# ignatova_telemetry_board.net
KiCad netlist of a schematic drawn in Altium Designer
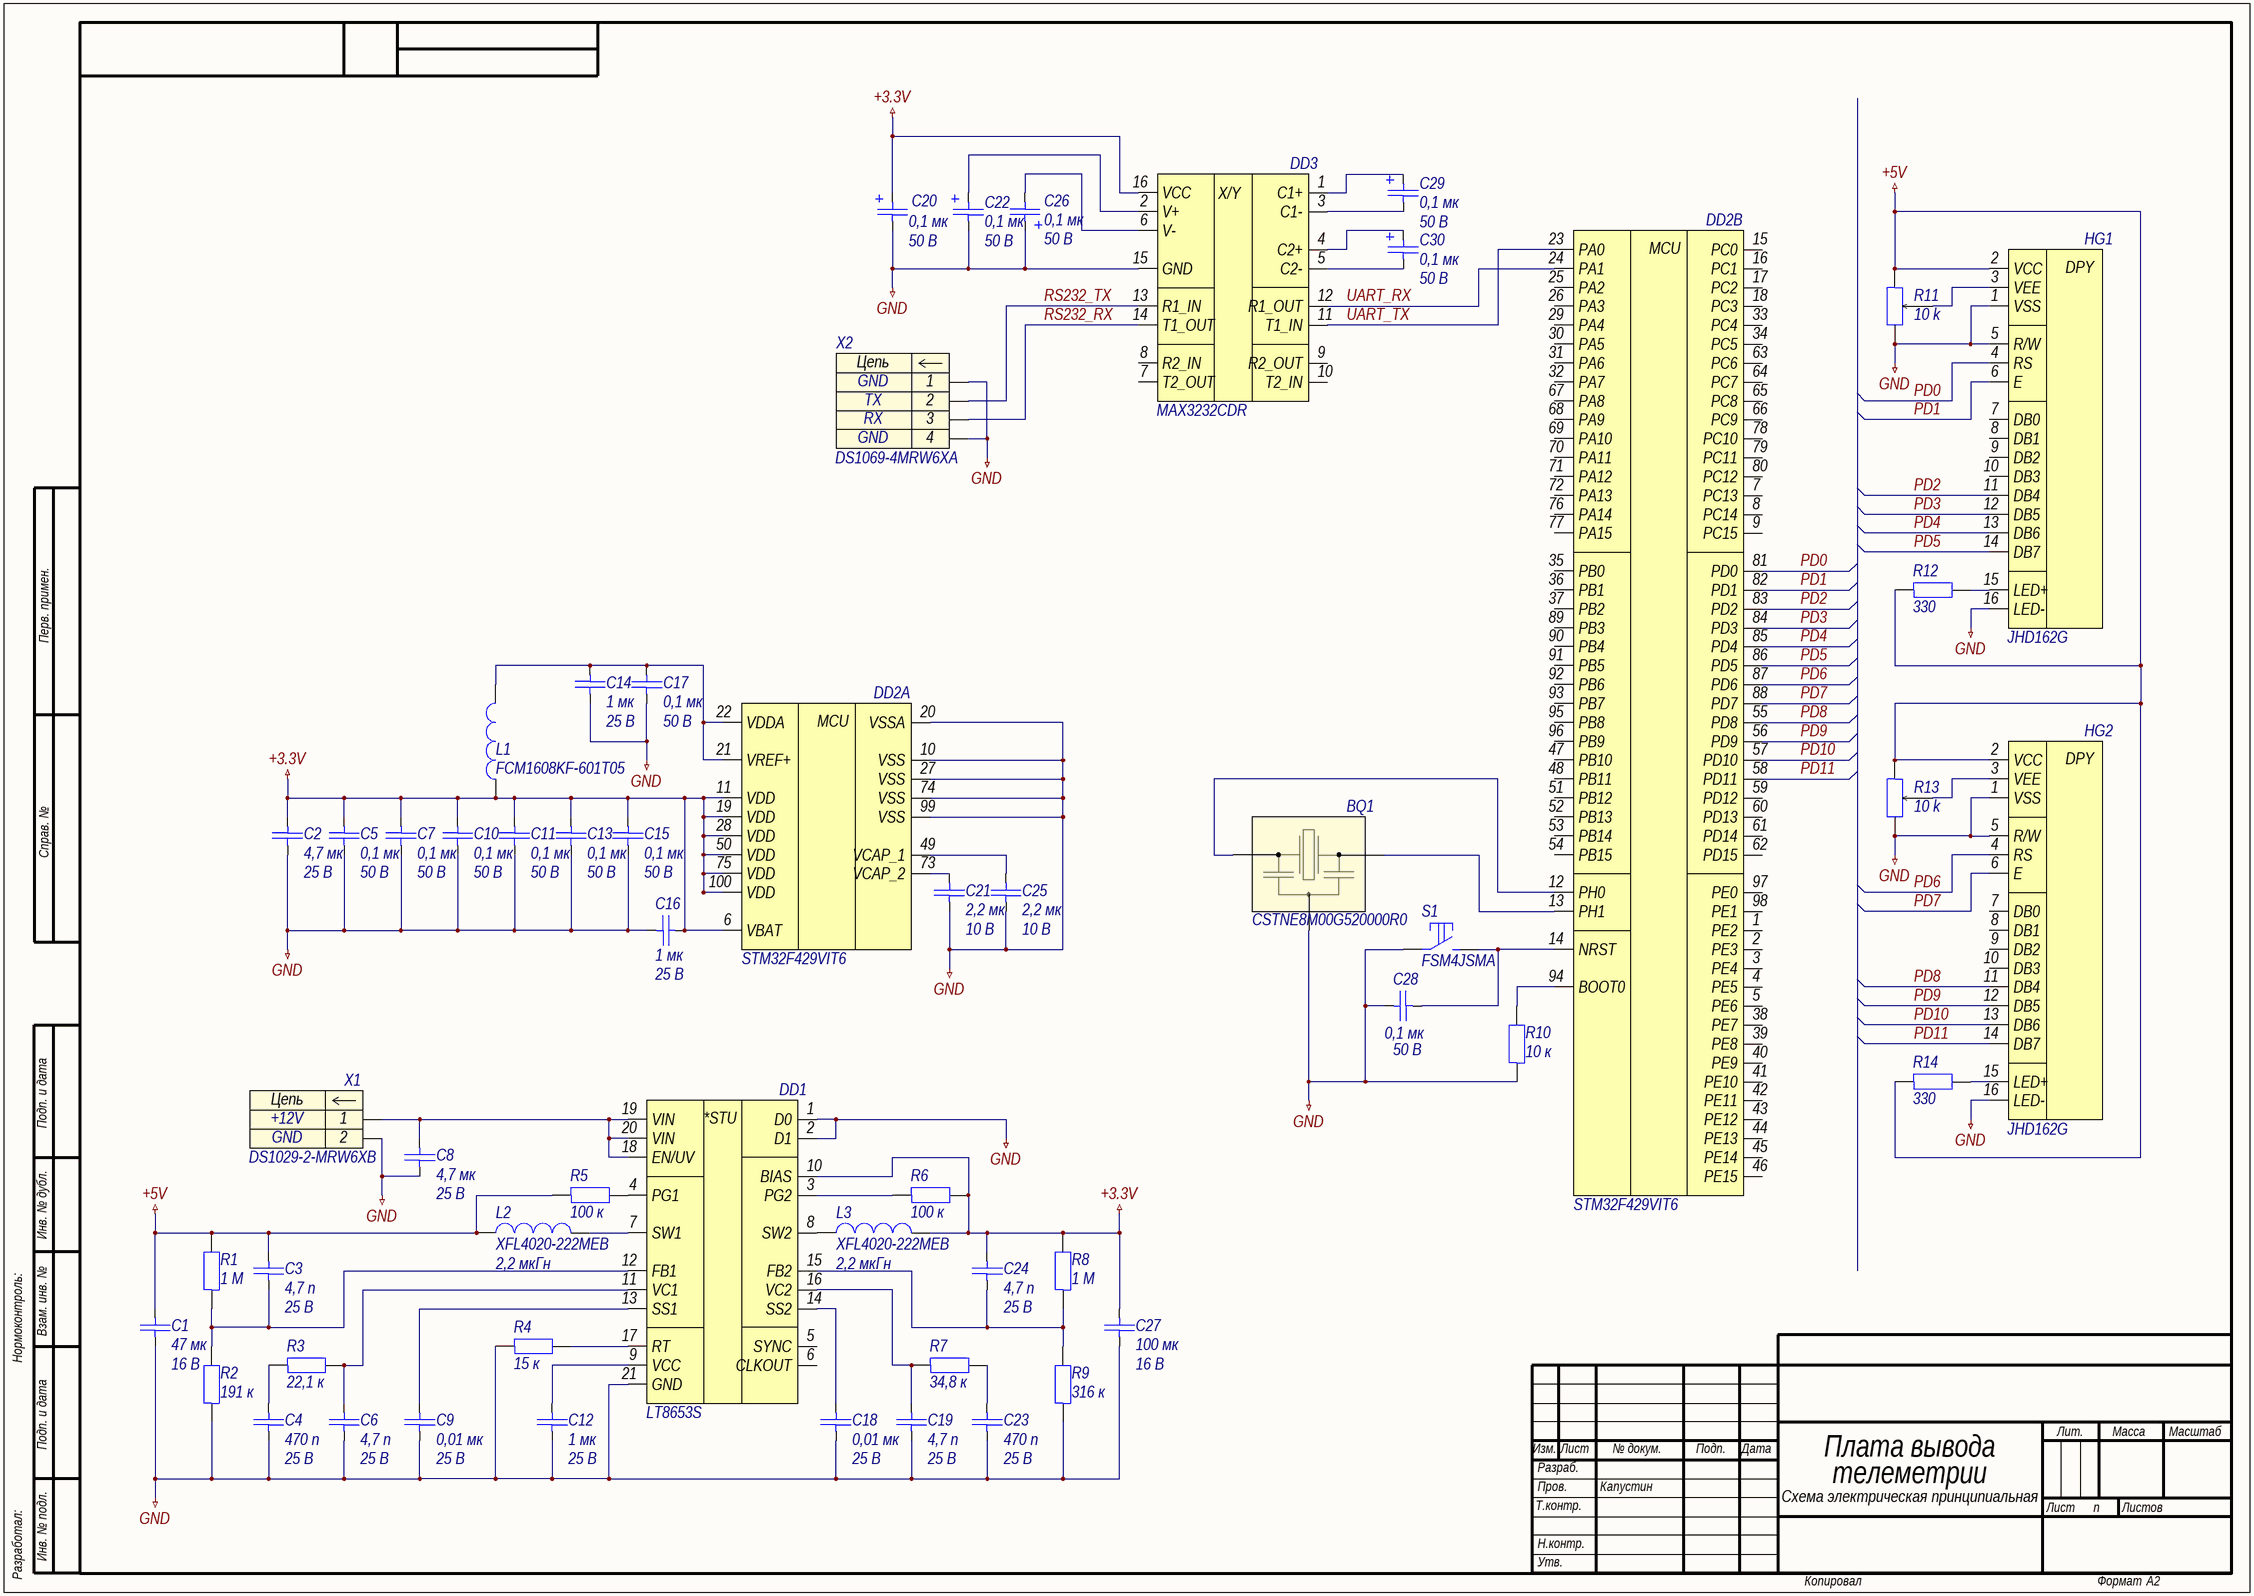
[diagram p0: ignatova_telemetry_board.SchDoc]

(export (version "E")
  (design (tool "Eeschema 10.0.6"))
  (components
    (comp (ref "BQ1")
      (value "CSTNE8M00G520000R0")
      (footprint "CSTNE-3-320X130X70")
      (description "=Описание")
      (libsource (lib "Database_Students") (part "CSTNE8M00G520000R0"))
    )
    (comp (ref "C1")
      (value "47 мк")
      (footprint "C1210")
      (description "=Описание")
      (fields (field (name "НАПРЯЖЕНИЕ") "16 В"))
      (libsource (lib "Database_Students") (part "C-NONPOLAR"))
    )
    (comp (ref "C2")
      (value "4,7 мк")
      (footprint "C0603")
      (description "=Описание")
      (fields (field (name "НАПРЯЖЕНИЕ") "25 В"))
      (libsource (lib "Database_Students") (part "C-NONPOLAR"))
    )
    (comp (ref "C3")
      (value "4,7 п")
      (footprint "C0201")
      (description "=Описание")
      (fields (field (name "НАПРЯЖЕНИЕ") "25 В"))
      (libsource (lib "Database_Students") (part "C-NONPOLAR"))
    )
    (comp (ref "C4")
      (value "470 п")
      (footprint "C0201")
      (description "=Описание")
      (fields (field (name "НАПРЯЖЕНИЕ") "25 В"))
      (libsource (lib "Database_Students") (part "C-NONPOLAR"))
    )
    (comp (ref "C5")
      (value "0,1 мк")
      (footprint "C0603")
      (description "=Описание")
      (fields (field (name "НАПРЯЖЕНИЕ") "50 В"))
      (libsource (lib "Database_Students") (part "C-NONPOLAR"))
    )
    (comp (ref "C6")
      (value "4,7 п")
      (footprint "C0201")
      (description "=Описание")
      (fields (field (name "НАПРЯЖЕНИЕ") "25 В"))
      (libsource (lib "Database_Students") (part "C-NONPOLAR"))
    )
    (comp (ref "C7")
      (value "0,1 мк")
      (footprint "C0603")
      (description "=Описание")
      (fields (field (name "НАПРЯЖЕНИЕ") "50 В"))
      (libsource (lib "Database_Students") (part "C-NONPOLAR"))
    )
    (comp (ref "C8")
      (value "4,7 мк")
      (footprint "C0603")
      (description "=Описание")
      (fields (field (name "НАПРЯЖЕНИЕ") "25 В"))
      (libsource (lib "Database_Students") (part "C-NONPOLAR"))
    )
    (comp (ref "C9")
      (value "0,01 мк")
      (footprint "C0201")
      (description "=Описание")
      (fields (field (name "НАПРЯЖЕНИЕ") "25 В"))
      (libsource (lib "Database_Students") (part "C-NONPOLAR"))
    )
    (comp (ref "C10")
      (value "0,1 мк")
      (footprint "C0603")
      (description "=Описание")
      (fields (field (name "НАПРЯЖЕНИЕ") "50 В"))
      (libsource (lib "Database_Students") (part "C-NONPOLAR"))
    )
    (comp (ref "C11")
      (value "0,1 мк")
      (footprint "C0603")
      (description "=Описание")
      (fields (field (name "НАПРЯЖЕНИЕ") "50 В"))
      (libsource (lib "Database_Students") (part "C-NONPOLAR"))
    )
    (comp (ref "C12")
      (value "1 мк")
      (footprint "C0603")
      (description "=Описание")
      (fields (field (name "НАПРЯЖЕНИЕ") "25 В"))
      (libsource (lib "Database_Students") (part "C-NONPOLAR"))
    )
    (comp (ref "C13")
      (value "0,1 мк")
      (footprint "C0603")
      (description "=Описание")
      (fields (field (name "НАПРЯЖЕНИЕ") "50 В"))
      (libsource (lib "Database_Students") (part "C-NONPOLAR"))
    )
    (comp (ref "C14")
      (value "1 мк")
      (footprint "C0603")
      (description "=Описание")
      (fields (field (name "НАПРЯЖЕНИЕ") "25 В"))
      (libsource (lib "Database_Students") (part "C-NONPOLAR"))
    )
    (comp (ref "C15")
      (value "0,1 мк")
      (footprint "C0603")
      (description "=Описание")
      (fields (field (name "НАПРЯЖЕНИЕ") "50 В"))
      (libsource (lib "Database_Students") (part "C-NONPOLAR"))
    )
    (comp (ref "C16")
      (value "1 мк")
      (footprint "C0603")
      (description "=Описание")
      (fields (field (name "НАПРЯЖЕНИЕ") "25 В"))
      (libsource (lib "Database_Students") (part "C-NONPOLAR"))
    )
    (comp (ref "C17")
      (value "0,1 мк")
      (footprint "C0603")
      (description "=Описание")
      (fields (field (name "НАПРЯЖЕНИЕ") "50 В"))
      (libsource (lib "Database_Students") (part "C-NONPOLAR"))
    )
    (comp (ref "C18")
      (value "0,01 мк")
      (footprint "C0201")
      (description "=Описание")
      (fields (field (name "НАПРЯЖЕНИЕ") "25 В"))
      (libsource (lib "Database_Students") (part "C-NONPOLAR"))
    )
    (comp (ref "C19")
      (value "4,7 п")
      (footprint "C0201")
      (description "=Описание")
      (fields (field (name "НАПРЯЖЕНИЕ") "25 В"))
      (libsource (lib "Database_Students") (part "C-NONPOLAR"))
    )
    (comp (ref "C20")
      (value "0,1 мк")
      (footprint "C1206POLAR")
      (description "=Описание")
      (fields (field (name "НАПРЯЖЕНИЕ") "50 В"))
      (libsource (lib "Database_Students") (part "C-POLAR"))
    )
    (comp (ref "C21")
      (value "2,2 мк")
      (footprint "C0603")
      (description "=Описание")
      (fields (field (name "НАПРЯЖЕНИЕ") "10 В"))
      (libsource (lib "Database_Students") (part "C-NONPOLAR"))
    )
    (comp (ref "C22")
      (value "0,1 мк")
      (footprint "C1206POLAR")
      (description "=Описание")
      (fields (field (name "НАПРЯЖЕНИЕ") "50 В"))
      (libsource (lib "Database_Students") (part "C-POLAR"))
    )
    (comp (ref "C23")
      (value "470 п")
      (footprint "C0201")
      (description "=Описание")
      (fields (field (name "НАПРЯЖЕНИЕ") "25 В"))
      (libsource (lib "Database_Students") (part "C-NONPOLAR"))
    )
    (comp (ref "C24")
      (value "4,7 п")
      (footprint "C0201")
      (description "=Описание")
      (fields (field (name "НАПРЯЖЕНИЕ") "25 В"))
      (libsource (lib "Database_Students") (part "C-NONPOLAR"))
    )
    (comp (ref "C25")
      (value "2,2 мк")
      (footprint "C0603")
      (description "=Описание")
      (fields (field (name "НАПРЯЖЕНИЕ") "10 В"))
      (libsource (lib "Database_Students") (part "C-NONPOLAR"))
    )
    (comp (ref "C26")
      (value "0,1 мк")
      (footprint "C1206POLAR")
      (description "=Описание")
      (fields (field (name "НАПРЯЖЕНИЕ") "50 В"))
      (libsource (lib "Database_Students") (part "C-POLAR"))
    )
    (comp (ref "C27")
      (value "100 мк")
      (footprint "C1210")
      (description "=Описание")
      (fields (field (name "НАПРЯЖЕНИЕ") "16 В"))
      (libsource (lib "Database_Students") (part "C-NONPOLAR"))
    )
    (comp (ref "C28")
      (value "0,1 мк")
      (footprint "C0603")
      (description "=Описание")
      (fields (field (name "НАПРЯЖЕНИЕ") "50 В"))
      (libsource (lib "Database_Students") (part "C-NONPOLAR"))
    )
    (comp (ref "C29")
      (value "0,1 мк")
      (footprint "C1206POLAR")
      (description "=Описание")
      (fields (field (name "НАПРЯЖЕНИЕ") "50 В"))
      (libsource (lib "Database_Students") (part "C-POLAR"))
    )
    (comp (ref "C30")
      (value "0,1 мк")
      (footprint "C1206POLAR")
      (description "=Описание")
      (fields (field (name "НАПРЯЖЕНИЕ") "50 В"))
      (libsource (lib "Database_Students") (part "C-POLAR"))
    )
    (comp (ref "DD1")
      (value "LT8653S")
      (footprint "LQFN-20")
      (description "=Описание")
      (libsource (lib "Database_Students") (part "LT8653S"))
    )
    (comp (ref "DD2")
      (value "STM32F429VIT6")
      (footprint "LQFP-100")
      (description "=Описание")
      (libsource (lib "stm32f429vit6") (part "STM32F429VIT6"))
    )
    (comp (ref "DD3")
      (value "MAX3232CDR")
      (footprint "SOIC-16")
      (description "=Описание")
      (libsource (lib "max3232cdr") (part "MAX3232CDR"))
    )
    (comp (ref "HG1")
      (value "JHD162G")
      (footprint "LCD-16x2")
      (description "=Описание")
      (libsource (lib "jhd162g") (part "JHD162G"))
    )
    (comp (ref "HG2")
      (value "JHD162G")
      (footprint "LCD-16x2")
      (description "=Описание")
      (libsource (lib "jhd162g") (part "JHD162G"))
    )
    (comp (ref "L1")
      (value "FCM1608KF-601T05")
      (footprint "BLM-2-0603")
      (description "=Описание")
      (libsource (lib "Database_Students") (part "FERRITE-BEAD"))
    )
    (comp (ref "L2")
      (value "XFL4020-222MEB")
      (footprint "XFL-2-430X430X210")
      (description "=Описание")
      (fields (field (name "ИНДУКТИВНОСТЬ") "2,2 мкГн"))
      (libsource (lib "Database_Students") (part "INDUCTOR-COMMON"))
    )
    (comp (ref "L3")
      (value "XFL4020-222MEB")
      (footprint "XFL-2-430X430X210")
      (description "=Описание")
      (fields (field (name "ИНДУКТИВНОСТЬ") "2,2 мкГн"))
      (libsource (lib "Database_Students") (part "INDUCTOR-COMMON"))
    )
    (comp (ref "R1")
      (value "1 М")
      (footprint "R0603")
      (description "=Описание")
      (libsource (lib "Database_Students") (part "R-COMMON"))
    )
    (comp (ref "R2")
      (value "191 к")
      (footprint "R0603")
      (description "=Описание")
      (libsource (lib "Database_Students") (part "R-COMMON"))
    )
    (comp (ref "R3")
      (value "22,1 к")
      (footprint "R0603")
      (description "=Описание")
      (libsource (lib "Database_Students") (part "R-COMMON"))
    )
    (comp (ref "R4")
      (value "15 к")
      (footprint "R0603")
      (description "=Описание")
      (libsource (lib "Database_Students") (part "R-COMMON"))
    )
    (comp (ref "R5")
      (value "100 к")
      (footprint "R0603")
      (description "=Описание")
      (libsource (lib "Database_Students") (part "R-COMMON"))
    )
    (comp (ref "R6")
      (value "100 к")
      (footprint "R0603")
      (description "=Описание")
      (libsource (lib "Database_Students") (part "R-COMMON"))
    )
    (comp (ref "R7")
      (value "34,8 к")
      (footprint "R0603")
      (description "=Описание")
      (libsource (lib "Database_Students") (part "R-COMMON"))
    )
    (comp (ref "R8")
      (value "1 М")
      (footprint "R0603")
      (description "=Описание")
      (libsource (lib "Database_Students") (part "R-COMMON"))
    )
    (comp (ref "R9")
      (value "316 к")
      (footprint "R0603")
      (description "=Описание")
      (libsource (lib "Database_Students") (part "R-COMMON"))
    )
    (comp (ref "R10")
      (value "10 к")
      (footprint "R0603")
      (description "=Описание")
      (libsource (lib "Database_Students") (part "R-COMMON"))
    )
    (comp (ref "R11")
      (value "10 k")
      (footprint "TRIMMER-RESISTOR")
      (description "=Описание")
      (libsource (lib "trimmer_resistor") (part "TRIMMER-RESISTOR"))
    )
    (comp (ref "R12")
      (value "330")
      (footprint "R0603")
      (description "=Описание")
      (libsource (lib "Database_Students") (part "R-COMMON"))
    )
    (comp (ref "R13")
      (value "10 k")
      (footprint "TRIMMER-RESISTOR")
      (description "=Описание")
      (libsource (lib "trimmer_resistor") (part "TRIMMER-RESISTOR"))
    )
    (comp (ref "R14")
      (value "330")
      (footprint "R0603")
      (description "=Описание")
      (libsource (lib "Database_Students") (part "R-COMMON"))
    )
    (comp (ref "S1")
      (value "FSM4JSMA")
      (footprint "FSM4JSMA")
      (description "=Описание")
      (libsource (lib "Database_Students") (part "SWITCH-01"))
    )
    (comp (ref "X1")
      (value "DS1029-2-MRW6XB")
      (footprint "DS1029-2-MRW6XB")
      (description "=Описание")
      (libsource (lib "Database_Students") (part "HEADER-2-PLG"))
    )
    (comp (ref "X2")
      (value "DS1069-4MRW6XA")
      (footprint "DS1069-4MRW6XA")
      (description "=Описание")
      (libsource (lib "Database_Students") (part "HEADER-4-PLG"))
    )
  )
  (nets
    (net (code "1") (name "+3.3V") (class "Default")
      (node (ref "C10") (pin "2") (pinfunction "2_2") (pintype "passive"))
      (node (ref "C11") (pin "2") (pinfunction "2_2") (pintype "passive"))
      (node (ref "C13") (pin "2") (pinfunction "2_2") (pintype "passive"))
      (node (ref "C15") (pin "2") (pinfunction "2_2") (pintype "passive"))
      (node (ref "C16") (pin "1") (pinfunction "1_1") (pintype "passive"))
      (node (ref "C2") (pin "2") (pinfunction "2_2") (pintype "passive"))
      (node (ref "C20") (pin "1") (pinfunction "1_1") (pintype "passive"))
      (node (ref "C24") (pin "1") (pinfunction "1_1") (pintype "passive"))
      (node (ref "C27") (pin "1") (pinfunction "1_1") (pintype "passive"))
      (node (ref "C5") (pin "2") (pinfunction "2_2") (pintype "passive"))
      (node (ref "C7") (pin "2") (pinfunction "2_2") (pintype "passive"))
      (node (ref "DD1") (pin "10") (pinfunction "BIAS_10") (pintype "passive"))
      (node (ref "DD2") (pin "100") (pinfunction "VDD_100") (pintype "passive"))
      (node (ref "DD2") (pin "11") (pinfunction "VDD_11") (pintype "passive"))
      (node (ref "DD2") (pin "19") (pinfunction "VDD_19") (pintype "passive"))
      (node (ref "DD2") (pin "28") (pinfunction "VDD_28") (pintype "passive"))
      (node (ref "DD2") (pin "50") (pinfunction "VDD_50") (pintype "passive"))
      (node (ref "DD2") (pin "6") (pinfunction "VBAT_6") (pintype "passive"))
      (node (ref "DD2") (pin "75") (pinfunction "VDD_75") (pintype "passive"))
      (node (ref "DD3") (pin "16") (pinfunction "VCC_16") (pintype "passive"))
      (node (ref "L1") (pin "1") (pinfunction "1_1") (pintype "passive"))
      (node (ref "L3") (pin "2") (pinfunction "2_2") (pintype "passive"))
      (node (ref "R6") (pin "2") (pinfunction "2_2") (pintype "passive"))
      (node (ref "R8") (pin "2") (pinfunction "2_2") (pintype "passive"))
    )
    (net (code "2") (name "+5V") (class "Default")
      (node (ref "C1") (pin "1") (pinfunction "1_1") (pintype "passive"))
      (node (ref "C3") (pin "1") (pinfunction "1_1") (pintype "passive"))
      (node (ref "HG1") (pin "2") (pinfunction "VCC_2") (pintype "passive"))
      (node (ref "HG2") (pin "2") (pinfunction "VCC_2") (pintype "passive"))
      (node (ref "L2") (pin "1") (pinfunction "1_1") (pintype "passive"))
      (node (ref "R1") (pin "2") (pinfunction "2_2") (pintype "passive"))
      (node (ref "R11") (pin "1") (pinfunction "1_1") (pintype "passive"))
      (node (ref "R12") (pin "1") (pinfunction "1_1") (pintype "passive"))
      (node (ref "R13") (pin "1") (pinfunction "1_1") (pintype "passive"))
      (node (ref "R14") (pin "1") (pinfunction "1_1") (pintype "passive"))
      (node (ref "R5") (pin "1") (pinfunction "1_1") (pintype "passive"))
    )
    (net (code "3") (name "/PD0") (class "Default")
      (node (ref "DD2") (pin "81") (pinfunction "PD0_81") (pintype "passive"))
      (node (ref "HG1") (pin "4") (pinfunction "RS_4") (pintype "passive"))
    )
    (net (code "4") (name "/PD1") (class "Default")
      (node (ref "DD2") (pin "82") (pinfunction "PD1_82") (pintype "passive"))
      (node (ref "HG1") (pin "6") (pinfunction "E_6") (pintype "passive"))
    )
    (net (code "5") (name "/PD2") (class "Default")
      (node (ref "DD2") (pin "83") (pinfunction "PD2_83") (pintype "passive"))
      (node (ref "HG1") (pin "11") (pinfunction "DB4_11") (pintype "passive"))
    )
    (net (code "6") (name "/PD3") (class "Default")
      (node (ref "DD2") (pin "84") (pinfunction "PD3_84") (pintype "passive"))
      (node (ref "HG1") (pin "12") (pinfunction "DB5_12") (pintype "passive"))
    )
    (net (code "7") (name "/PD4") (class "Default")
      (node (ref "DD2") (pin "85") (pinfunction "PD4_85") (pintype "passive"))
      (node (ref "HG1") (pin "13") (pinfunction "DB6_13") (pintype "passive"))
    )
    (net (code "8") (name "/PD5") (class "Default")
      (node (ref "DD2") (pin "86") (pinfunction "PD5_86") (pintype "passive"))
      (node (ref "HG1") (pin "14") (pinfunction "DB7_14") (pintype "passive"))
    )
    (net (code "9") (name "/PD6") (class "Default")
      (node (ref "DD2") (pin "87") (pinfunction "PD6_87") (pintype "passive"))
      (node (ref "HG2") (pin "4") (pinfunction "RS_4") (pintype "passive"))
    )
    (net (code "10") (name "/PD7") (class "Default")
      (node (ref "DD2") (pin "88") (pinfunction "PD7_88") (pintype "passive"))
      (node (ref "HG2") (pin "6") (pinfunction "E_6") (pintype "passive"))
    )
    (net (code "11") (name "/PD8") (class "Default")
      (node (ref "DD2") (pin "55") (pinfunction "PD8_55") (pintype "passive"))
      (node (ref "HG2") (pin "11") (pinfunction "DB4_11") (pintype "passive"))
    )
    (net (code "12") (name "/PD9") (class "Default")
      (node (ref "DD2") (pin "56") (pinfunction "PD9_56") (pintype "passive"))
      (node (ref "HG2") (pin "12") (pinfunction "DB5_12") (pintype "passive"))
    )
    (net (code "13") (name "/PD10") (class "Default")
      (node (ref "DD2") (pin "57") (pinfunction "PD10_57") (pintype "passive"))
      (node (ref "HG2") (pin "13") (pinfunction "DB6_13") (pintype "passive"))
    )
    (net (code "14") (name "/PD11") (class "Default")
      (node (ref "DD2") (pin "58") (pinfunction "PD11_58") (pintype "passive"))
      (node (ref "HG2") (pin "14") (pinfunction "DB7_14") (pintype "passive"))
    )
    (net (code "15") (name "/RS232_RX") (class "Default")
      (node (ref "DD3") (pin "14") (pinfunction "T1_OUT_14") (pintype "passive"))
      (node (ref "X2") (pin "3") (pinfunction "3_3") (pintype "passive"))
    )
    (net (code "16") (name "/RS232_TX") (class "Default")
      (node (ref "DD3") (pin "13") (pinfunction "R1_IN_13") (pintype "passive"))
      (node (ref "X2") (pin "2") (pinfunction "2_2") (pintype "passive"))
    )
    (net (code "17") (name "/UART_RX") (class "Default")
      (node (ref "DD2") (pin "24") (pinfunction "PA1_24") (pintype "passive"))
      (node (ref "DD3") (pin "12") (pinfunction "R1_OUT_12") (pintype "passive"))
    )
    (net (code "18") (name "/UART_TX") (class "Default")
      (node (ref "DD2") (pin "23") (pinfunction "PA0_23") (pintype "passive"))
      (node (ref "DD3") (pin "11") (pinfunction "T1_IN_11") (pintype "passive"))
    )
    (net (code "19") (name "GND") (class "Default")
      (node (ref "BQ1") (pin "2") (pinfunction "2_2") (pintype "passive"))
      (node (ref "C1") (pin "2") (pinfunction "2_2") (pintype "passive"))
      (node (ref "C10") (pin "1") (pinfunction "1_1") (pintype "passive"))
      (node (ref "C11") (pin "1") (pinfunction "1_1") (pintype "passive"))
      (node (ref "C12") (pin "2") (pinfunction "2_2") (pintype "passive"))
      (node (ref "C13") (pin "1") (pinfunction "1_1") (pintype "passive"))
      (node (ref "C14") (pin "1") (pinfunction "1_1") (pintype "passive"))
      (node (ref "C15") (pin "1") (pinfunction "1_1") (pintype "passive"))
      (node (ref "C16") (pin "2") (pinfunction "2_2") (pintype "passive"))
      (node (ref "C17") (pin "2") (pinfunction "2_2") (pintype "passive"))
      (node (ref "C18") (pin "2") (pinfunction "2_2") (pintype "passive"))
      (node (ref "C19") (pin "2") (pinfunction "2_2") (pintype "passive"))
      (node (ref "C2") (pin "1") (pinfunction "1_1") (pintype "passive"))
      (node (ref "C20") (pin "2") (pinfunction "2_2") (pintype "passive"))
      (node (ref "C21") (pin "2") (pinfunction "2_2") (pintype "passive"))
      (node (ref "C22") (pin "2") (pinfunction "2_2") (pintype "passive"))
      (node (ref "C23") (pin "2") (pinfunction "2_2") (pintype "passive"))
      (node (ref "C25") (pin "2") (pinfunction "2_2") (pintype "passive"))
      (node (ref "C26") (pin "1") (pinfunction "1_1") (pintype "passive"))
      (node (ref "C27") (pin "2") (pinfunction "2_2") (pintype "passive"))
      (node (ref "C28") (pin "1") (pinfunction "1_1") (pintype "passive"))
      (node (ref "C4") (pin "2") (pinfunction "2_2") (pintype "passive"))
      (node (ref "C5") (pin "1") (pinfunction "1_1") (pintype "passive"))
      (node (ref "C6") (pin "2") (pinfunction "2_2") (pintype "passive"))
      (node (ref "C7") (pin "1") (pinfunction "1_1") (pintype "passive"))
      (node (ref "C8") (pin "2") (pinfunction "2_2") (pintype "passive"))
      (node (ref "C9") (pin "2") (pinfunction "2_2") (pintype "passive"))
      (node (ref "DD1") (pin "1") (pinfunction "D0_1") (pintype "passive"))
      (node (ref "DD1") (pin "2") (pinfunction "D1_2") (pintype "passive"))
      (node (ref "DD1") (pin "21") (pinfunction "GND_21") (pintype "passive"))
      (node (ref "DD2") (pin "10") (pinfunction "VSS_10") (pintype "passive"))
      (node (ref "DD2") (pin "20") (pinfunction "VSSA_20") (pintype "passive"))
      (node (ref "DD2") (pin "27") (pinfunction "VSS_27") (pintype "passive"))
      (node (ref "DD2") (pin "74") (pinfunction "VSS_74") (pintype "passive"))
      (node (ref "DD2") (pin "99") (pinfunction "VSS_99") (pintype "passive"))
      (node (ref "DD3") (pin "15") (pinfunction "GND_15") (pintype "passive"))
      (node (ref "HG1") (pin "1") (pinfunction "VSS_1") (pintype "passive"))
      (node (ref "HG1") (pin "16") (pinfunction "LED-_16") (pintype "passive"))
      (node (ref "HG1") (pin "5") (pinfunction "R/W_5") (pintype "passive"))
      (node (ref "HG2") (pin "1") (pinfunction "VSS_1") (pintype "passive"))
      (node (ref "HG2") (pin "16") (pinfunction "LED-_16") (pintype "passive"))
      (node (ref "HG2") (pin "5") (pinfunction "R/W_5") (pintype "passive"))
      (node (ref "R10") (pin "1") (pinfunction "1_1") (pintype "passive"))
      (node (ref "R11") (pin "3") (pinfunction "3_3") (pintype "passive"))
      (node (ref "R13") (pin "3") (pinfunction "3_3") (pintype "passive"))
      (node (ref "R2") (pin "1") (pinfunction "1_1") (pintype "passive"))
      (node (ref "R4") (pin "1") (pinfunction "1_1") (pintype "passive"))
      (node (ref "R9") (pin "1") (pinfunction "1_1") (pintype "passive"))
      (node (ref "S1") (pin "1") (pinfunction "1_1") (pintype "passive"))
      (node (ref "X1") (pin "2") (pinfunction "2_2") (pintype "passive"))
      (node (ref "X2") (pin "1") (pinfunction "1_1") (pintype "passive"))
      (node (ref "X2") (pin "4") (pinfunction "4_4") (pintype "passive"))
    )
    (net (code "20") (name "Net-(C4-Pad1)") (class "Default")
      (node (ref "C4") (pin "1") (pinfunction "1_1") (pintype "passive"))
      (node (ref "R3") (pin "1") (pinfunction "1_1") (pintype "passive"))
    )
    (net (code "21") (name "Net-(C23-Pad1)") (class "Default")
      (node (ref "C23") (pin "1") (pinfunction "1_1") (pintype "passive"))
      (node (ref "R7") (pin "2") (pinfunction "2_2") (pintype "passive"))
    )
    (net (code "22") (name "Net-(DD1-EN{slash}UV)") (class "Default")
      (node (ref "C8") (pin "1") (pinfunction "1_1") (pintype "passive"))
      (node (ref "DD1") (pin "18") (pinfunction "EN/UV_18") (pintype "passive"))
      (node (ref "DD1") (pin "19") (pinfunction "VIN_19") (pintype "passive"))
      (node (ref "DD1") (pin "20") (pinfunction "VIN_20") (pintype "passive"))
      (node (ref "X1") (pin "1") (pinfunction "1_1") (pintype "passive"))
    )
    (net (code "23") (name "Net-(DD1-FB1)") (class "Default")
      (node (ref "C3") (pin "2") (pinfunction "2_2") (pintype "passive"))
      (node (ref "DD1") (pin "12") (pinfunction "FB1_12") (pintype "passive"))
      (node (ref "R1") (pin "1") (pinfunction "1_1") (pintype "passive"))
      (node (ref "R2") (pin "2") (pinfunction "2_2") (pintype "passive"))
    )
    (net (code "24") (name "Net-(DD1-FB2)") (class "Default")
      (node (ref "C24") (pin "2") (pinfunction "2_2") (pintype "passive"))
      (node (ref "DD1") (pin "15") (pinfunction "FB2_15") (pintype "passive"))
      (node (ref "R8") (pin "1") (pinfunction "1_1") (pintype "passive"))
      (node (ref "R9") (pin "2") (pinfunction "2_2") (pintype "passive"))
    )
    (net (code "25") (name "Net-(DD1-PG1)") (class "Default")
      (node (ref "DD1") (pin "4") (pinfunction "PG1_4") (pintype "passive"))
      (node (ref "R5") (pin "2") (pinfunction "2_2") (pintype "passive"))
    )
    (net (code "26") (name "Net-(DD1-PG2)") (class "Default")
      (node (ref "DD1") (pin "3") (pinfunction "PG2_3") (pintype "passive"))
      (node (ref "R6") (pin "1") (pinfunction "1_1") (pintype "passive"))
    )
    (net (code "27") (name "Net-(DD1-RT)") (class "Default")
      (node (ref "DD1") (pin "17") (pinfunction "RT_17") (pintype "passive"))
      (node (ref "R4") (pin "2") (pinfunction "2_2") (pintype "passive"))
    )
    (net (code "28") (name "Net-(DD1-SS1)") (class "Default")
      (node (ref "C9") (pin "1") (pinfunction "1_1") (pintype "passive"))
      (node (ref "DD1") (pin "13") (pinfunction "SS1_13") (pintype "passive"))
    )
    (net (code "29") (name "Net-(DD1-SS2)") (class "Default")
      (node (ref "C18") (pin "1") (pinfunction "1_1") (pintype "passive"))
      (node (ref "DD1") (pin "14") (pinfunction "SS2_14") (pintype "passive"))
    )
    (net (code "30") (name "Net-(DD1-SW1)") (class "Default")
      (node (ref "DD1") (pin "7") (pinfunction "SW1_7") (pintype "passive"))
      (node (ref "L2") (pin "2") (pinfunction "2_2") (pintype "passive"))
    )
    (net (code "31") (name "Net-(DD1-SW2)") (class "Default")
      (node (ref "DD1") (pin "8") (pinfunction "SW2_8") (pintype "passive"))
      (node (ref "L3") (pin "1") (pinfunction "1_1") (pintype "passive"))
    )
    (net (code "32") (name "Net-(DD1-VC1)") (class "Default")
      (node (ref "C6") (pin "1") (pinfunction "1_1") (pintype "passive"))
      (node (ref "DD1") (pin "11") (pinfunction "VC1_11") (pintype "passive"))
      (node (ref "R3") (pin "2") (pinfunction "2_2") (pintype "passive"))
    )
    (net (code "33") (name "Net-(DD1-VC2)") (class "Default")
      (node (ref "C19") (pin "1") (pinfunction "1_1") (pintype "passive"))
      (node (ref "DD1") (pin "16") (pinfunction "VC2_16") (pintype "passive"))
      (node (ref "R7") (pin "1") (pinfunction "1_1") (pintype "passive"))
    )
    (net (code "34") (name "Net-(DD1-VCC)") (class "Default")
      (node (ref "C12") (pin "1") (pinfunction "1_1") (pintype "passive"))
      (node (ref "DD1") (pin "9") (pinfunction "VCC_9") (pintype "passive"))
    )
    (net (code "35") (name "Net-(DD2A-VCAP_1)") (class "Default")
      (node (ref "C25") (pin "1") (pinfunction "1_1") (pintype "passive"))
      (node (ref "DD2") (pin "49") (pinfunction "VCAP_1_49") (pintype "passive"))
    )
    (net (code "36") (name "Net-(DD2A-VCAP_2)") (class "Default")
      (node (ref "C21") (pin "1") (pinfunction "1_1") (pintype "passive"))
      (node (ref "DD2") (pin "73") (pinfunction "VCAP_2_73") (pintype "passive"))
    )
    (net (code "37") (name "Net-(DD2A-VDDA)") (class "Default")
      (node (ref "C14") (pin "2") (pinfunction "2_2") (pintype "passive"))
      (node (ref "C17") (pin "1") (pinfunction "1_1") (pintype "passive"))
      (node (ref "DD2") (pin "21") (pinfunction "VREF+_21") (pintype "passive"))
      (node (ref "DD2") (pin "22") (pinfunction "VDDA_22") (pintype "passive"))
      (node (ref "L1") (pin "2") (pinfunction "2_2") (pintype "passive"))
    )
    (net (code "38") (name "Net-(DD2B-BOOT0)") (class "Default")
      (node (ref "DD2") (pin "94") (pinfunction "BOOT0_94") (pintype "passive"))
      (node (ref "R10") (pin "2") (pinfunction "2_2") (pintype "passive"))
    )
    (net (code "39") (name "Net-(DD2B-NRST)") (class "Default")
      (node (ref "C28") (pin "2") (pinfunction "2_2") (pintype "passive"))
      (node (ref "DD2") (pin "14") (pinfunction "NRST_14") (pintype "passive"))
      (node (ref "S1") (pin "2") (pinfunction "2_2") (pintype "passive"))
    )
    (net (code "40") (name "Net-(DD2B-PH0)") (class "Default")
      (node (ref "BQ1") (pin "3") (pinfunction "3_3") (pintype "passive"))
      (node (ref "DD2") (pin "12") (pinfunction "PH0_12") (pintype "passive"))
    )
    (net (code "41") (name "Net-(DD2B-PH1)") (class "Default")
      (node (ref "BQ1") (pin "1") (pinfunction "1_1") (pintype "passive"))
      (node (ref "DD2") (pin "13") (pinfunction "PH1_13") (pintype "passive"))
    )
    (net (code "42") (name "Net-(DD3-C1+)") (class "Default")
      (node (ref "C29") (pin "1") (pinfunction "1_1") (pintype "passive"))
      (node (ref "DD3") (pin "1") (pinfunction "C1+_1") (pintype "passive"))
    )
    (net (code "43") (name "Net-(DD3-C1-)") (class "Default")
      (node (ref "C29") (pin "2") (pinfunction "2_2") (pintype "passive"))
      (node (ref "DD3") (pin "3") (pinfunction "C1-_3") (pintype "passive"))
    )
    (net (code "44") (name "Net-(DD3-C2+)") (class "Default")
      (node (ref "C30") (pin "1") (pinfunction "1_1") (pintype "passive"))
      (node (ref "DD3") (pin "4") (pinfunction "C2+_4") (pintype "passive"))
    )
    (net (code "45") (name "Net-(DD3-C2-)") (class "Default")
      (node (ref "C30") (pin "2") (pinfunction "2_2") (pintype "passive"))
      (node (ref "DD3") (pin "5") (pinfunction "C2-_5") (pintype "passive"))
    )
    (net (code "46") (name "Net-(DD3-V+)") (class "Default")
      (node (ref "C22") (pin "1") (pinfunction "1_1") (pintype "passive"))
      (node (ref "DD3") (pin "2") (pinfunction "V+_2") (pintype "passive"))
    )
    (net (code "47") (name "Net-(DD3-V-)") (class "Default")
      (node (ref "C26") (pin "2") (pinfunction "2_2") (pintype "passive"))
      (node (ref "DD3") (pin "6") (pinfunction "V-_6") (pintype "passive"))
    )
    (net (code "48") (name "Net-(HG1-LED+)") (class "Default")
      (node (ref "HG1") (pin "15") (pinfunction "LED+_15") (pintype "passive"))
      (node (ref "R12") (pin "2") (pinfunction "2_2") (pintype "passive"))
    )
    (net (code "49") (name "Net-(HG1-VEE)") (class "Default")
      (node (ref "HG1") (pin "3") (pinfunction "VEE_3") (pintype "passive"))
      (node (ref "R11") (pin "2") (pinfunction "2_2") (pintype "passive"))
    )
    (net (code "50") (name "Net-(HG2-LED+)") (class "Default")
      (node (ref "HG2") (pin "15") (pinfunction "LED+_15") (pintype "passive"))
      (node (ref "R14") (pin "2") (pinfunction "2_2") (pintype "passive"))
    )
    (net (code "51") (name "Net-(HG2-VEE)") (class "Default")
      (node (ref "HG2") (pin "3") (pinfunction "VEE_3") (pintype "passive"))
      (node (ref "R13") (pin "2") (pinfunction "2_2") (pintype "passive"))
    )
    (net (code "52") (name "unconnected-(DD1-CLKOUT-Pad6)") (class "Default")
      (node (ref "DD1") (pin "6") (pinfunction "CLKOUT_6") (pintype "passive"))
    )
    (net (code "53") (name "unconnected-(DD1-SYNC-Pad5)") (class "Default")
      (node (ref "DD1") (pin "5") (pinfunction "SYNC_5") (pintype "passive"))
    )
    (net (code "54") (name "unconnected-(DD2B-PA2-Pad25)") (class "Default")
      (node (ref "DD2") (pin "25") (pinfunction "PA2_25") (pintype "passive"))
    )
    (net (code "55") (name "unconnected-(DD2B-PA3-Pad26)") (class "Default")
      (node (ref "DD2") (pin "26") (pinfunction "PA3_26") (pintype "passive"))
    )
    (net (code "56") (name "unconnected-(DD2B-PA4-Pad29)") (class "Default")
      (node (ref "DD2") (pin "29") (pinfunction "PA4_29") (pintype "passive"))
    )
    (net (code "57") (name "unconnected-(DD2B-PA5-Pad30)") (class "Default")
      (node (ref "DD2") (pin "30") (pinfunction "PA5_30") (pintype "passive"))
    )
    (net (code "58") (name "unconnected-(DD2B-PA6-Pad31)") (class "Default")
      (node (ref "DD2") (pin "31") (pinfunction "PA6_31") (pintype "passive"))
    )
    (net (code "59") (name "unconnected-(DD2B-PA7-Pad32)") (class "Default")
      (node (ref "DD2") (pin "32") (pinfunction "PA7_32") (pintype "passive"))
    )
    (net (code "60") (name "unconnected-(DD2B-PA8-Pad67)") (class "Default")
      (node (ref "DD2") (pin "67") (pinfunction "PA8_67") (pintype "passive"))
    )
    (net (code "61") (name "unconnected-(DD2B-PA9-Pad68)") (class "Default")
      (node (ref "DD2") (pin "68") (pinfunction "PA9_68") (pintype "passive"))
    )
    (net (code "62") (name "unconnected-(DD2B-PA10-Pad69)") (class "Default")
      (node (ref "DD2") (pin "69") (pinfunction "PA10_69") (pintype "passive"))
    )
    (net (code "63") (name "unconnected-(DD2B-PA11-Pad70)") (class "Default")
      (node (ref "DD2") (pin "70") (pinfunction "PA11_70") (pintype "passive"))
    )
    (net (code "64") (name "unconnected-(DD2B-PA12-Pad71)") (class "Default")
      (node (ref "DD2") (pin "71") (pinfunction "PA12_71") (pintype "passive"))
    )
    (net (code "65") (name "unconnected-(DD2B-PA13-Pad72)") (class "Default")
      (node (ref "DD2") (pin "72") (pinfunction "PA13_72") (pintype "passive"))
    )
    (net (code "66") (name "unconnected-(DD2B-PA14-Pad76)") (class "Default")
      (node (ref "DD2") (pin "76") (pinfunction "PA14_76") (pintype "passive"))
    )
    (net (code "67") (name "unconnected-(DD2B-PA15-Pad77)") (class "Default")
      (node (ref "DD2") (pin "77") (pinfunction "PA15_77") (pintype "passive"))
    )
    (net (code "68") (name "unconnected-(DD2B-PB0-Pad35)") (class "Default")
      (node (ref "DD2") (pin "35") (pinfunction "PB0_35") (pintype "passive"))
    )
    (net (code "69") (name "unconnected-(DD2B-PB1-Pad36)") (class "Default")
      (node (ref "DD2") (pin "36") (pinfunction "PB1_36") (pintype "passive"))
    )
    (net (code "70") (name "unconnected-(DD2B-PB2-Pad37)") (class "Default")
      (node (ref "DD2") (pin "37") (pinfunction "PB2_37") (pintype "passive"))
    )
    (net (code "71") (name "unconnected-(DD2B-PB3-Pad89)") (class "Default")
      (node (ref "DD2") (pin "89") (pinfunction "PB3_89") (pintype "passive"))
    )
    (net (code "72") (name "unconnected-(DD2B-PB4-Pad90)") (class "Default")
      (node (ref "DD2") (pin "90") (pinfunction "PB4_90") (pintype "passive"))
    )
    (net (code "73") (name "unconnected-(DD2B-PB5-Pad91)") (class "Default")
      (node (ref "DD2") (pin "91") (pinfunction "PB5_91") (pintype "passive"))
    )
    (net (code "74") (name "unconnected-(DD2B-PB6-Pad92)") (class "Default")
      (node (ref "DD2") (pin "92") (pinfunction "PB6_92") (pintype "passive"))
    )
    (net (code "75") (name "unconnected-(DD2B-PB7-Pad93)") (class "Default")
      (node (ref "DD2") (pin "93") (pinfunction "PB7_93") (pintype "passive"))
    )
    (net (code "76") (name "unconnected-(DD2B-PB8-Pad95)") (class "Default")
      (node (ref "DD2") (pin "95") (pinfunction "PB8_95") (pintype "passive"))
    )
    (net (code "77") (name "unconnected-(DD2B-PB9-Pad96)") (class "Default")
      (node (ref "DD2") (pin "96") (pinfunction "PB9_96") (pintype "passive"))
    )
    (net (code "78") (name "unconnected-(DD2B-PB10-Pad47)") (class "Default")
      (node (ref "DD2") (pin "47") (pinfunction "PB10_47") (pintype "passive"))
    )
    (net (code "79") (name "unconnected-(DD2B-PB11-Pad48)") (class "Default")
      (node (ref "DD2") (pin "48") (pinfunction "PB11_48") (pintype "passive"))
    )
    (net (code "80") (name "unconnected-(DD2B-PB12-Pad51)") (class "Default")
      (node (ref "DD2") (pin "51") (pinfunction "PB12_51") (pintype "passive"))
    )
    (net (code "81") (name "unconnected-(DD2B-PB13-Pad52)") (class "Default")
      (node (ref "DD2") (pin "52") (pinfunction "PB13_52") (pintype "passive"))
    )
    (net (code "82") (name "unconnected-(DD2B-PB14-Pad53)") (class "Default")
      (node (ref "DD2") (pin "53") (pinfunction "PB14_53") (pintype "passive"))
    )
    (net (code "83") (name "unconnected-(DD2B-PB15-Pad54)") (class "Default")
      (node (ref "DD2") (pin "54") (pinfunction "PB15_54") (pintype "passive"))
    )
    (net (code "84") (name "unconnected-(DD2B-PC0-Pad15)") (class "Default")
      (node (ref "DD2") (pin "15") (pinfunction "PC0_15") (pintype "passive"))
    )
    (net (code "85") (name "unconnected-(DD2B-PC1-Pad16)") (class "Default")
      (node (ref "DD2") (pin "16") (pinfunction "PC1_16") (pintype "passive"))
    )
    (net (code "86") (name "unconnected-(DD2B-PC2-Pad17)") (class "Default")
      (node (ref "DD2") (pin "17") (pinfunction "PC2_17") (pintype "passive"))
    )
    (net (code "87") (name "unconnected-(DD2B-PC3-Pad18)") (class "Default")
      (node (ref "DD2") (pin "18") (pinfunction "PC3_18") (pintype "passive"))
    )
    (net (code "88") (name "unconnected-(DD2B-PC4-Pad33)") (class "Default")
      (node (ref "DD2") (pin "33") (pinfunction "PC4_33") (pintype "passive"))
    )
    (net (code "89") (name "unconnected-(DD2B-PC5-Pad34)") (class "Default")
      (node (ref "DD2") (pin "34") (pinfunction "PC5_34") (pintype "passive"))
    )
    (net (code "90") (name "unconnected-(DD2B-PC6-Pad63)") (class "Default")
      (node (ref "DD2") (pin "63") (pinfunction "PC6_63") (pintype "passive"))
    )
    (net (code "91") (name "unconnected-(DD2B-PC7-Pad64)") (class "Default")
      (node (ref "DD2") (pin "64") (pinfunction "PC7_64") (pintype "passive"))
    )
    (net (code "92") (name "unconnected-(DD2B-PC8-Pad65)") (class "Default")
      (node (ref "DD2") (pin "65") (pinfunction "PC8_65") (pintype "passive"))
    )
    (net (code "93") (name "unconnected-(DD2B-PC9-Pad66)") (class "Default")
      (node (ref "DD2") (pin "66") (pinfunction "PC9_66") (pintype "passive"))
    )
    (net (code "94") (name "unconnected-(DD2B-PC10-Pad78)") (class "Default")
      (node (ref "DD2") (pin "78") (pinfunction "PC10_78") (pintype "passive"))
    )
    (net (code "95") (name "unconnected-(DD2B-PC11-Pad79)") (class "Default")
      (node (ref "DD2") (pin "79") (pinfunction "PC11_79") (pintype "passive"))
    )
    (net (code "96") (name "unconnected-(DD2B-PC12-Pad80)") (class "Default")
      (node (ref "DD2") (pin "80") (pinfunction "PC12_80") (pintype "passive"))
    )
    (net (code "97") (name "unconnected-(DD2B-PC13-Pad7)") (class "Default")
      (node (ref "DD2") (pin "7") (pinfunction "PC13_7") (pintype "passive"))
    )
    (net (code "98") (name "unconnected-(DD2B-PC14-Pad8)") (class "Default")
      (node (ref "DD2") (pin "8") (pinfunction "PC14_8") (pintype "passive"))
    )
    (net (code "99") (name "unconnected-(DD2B-PC15-Pad9)") (class "Default")
      (node (ref "DD2") (pin "9") (pinfunction "PC15_9") (pintype "passive"))
    )
    (net (code "100") (name "unconnected-(DD2B-PD12-Pad59)") (class "Default")
      (node (ref "DD2") (pin "59") (pinfunction "PD12_59") (pintype "passive"))
    )
    (net (code "101") (name "unconnected-(DD2B-PD13-Pad60)") (class "Default")
      (node (ref "DD2") (pin "60") (pinfunction "PD13_60") (pintype "passive"))
    )
    (net (code "102") (name "unconnected-(DD2B-PD14-Pad61)") (class "Default")
      (node (ref "DD2") (pin "61") (pinfunction "PD14_61") (pintype "passive"))
    )
    (net (code "103") (name "unconnected-(DD2B-PD15-Pad62)") (class "Default")
      (node (ref "DD2") (pin "62") (pinfunction "PD15_62") (pintype "passive"))
    )
    (net (code "104") (name "unconnected-(DD2B-PE0-Pad97)") (class "Default")
      (node (ref "DD2") (pin "97") (pinfunction "PE0_97") (pintype "passive"))
    )
    (net (code "105") (name "unconnected-(DD2B-PE1-Pad98)") (class "Default")
      (node (ref "DD2") (pin "98") (pinfunction "PE1_98") (pintype "passive"))
    )
    (net (code "106") (name "unconnected-(DD2B-PE2-Pad1)") (class "Default")
      (node (ref "DD2") (pin "1") (pinfunction "PE2_1") (pintype "passive"))
    )
    (net (code "107") (name "unconnected-(DD2B-PE3-Pad2)") (class "Default")
      (node (ref "DD2") (pin "2") (pinfunction "PE3_2") (pintype "passive"))
    )
    (net (code "108") (name "unconnected-(DD2B-PE4-Pad3)") (class "Default")
      (node (ref "DD2") (pin "3") (pinfunction "PE4_3") (pintype "passive"))
    )
    (net (code "109") (name "unconnected-(DD2B-PE5-Pad4)") (class "Default")
      (node (ref "DD2") (pin "4") (pinfunction "PE5_4") (pintype "passive"))
    )
    (net (code "110") (name "unconnected-(DD2B-PE6-Pad5)") (class "Default")
      (node (ref "DD2") (pin "5") (pinfunction "PE6_5") (pintype "passive"))
    )
    (net (code "111") (name "unconnected-(DD2B-PE7-Pad38)") (class "Default")
      (node (ref "DD2") (pin "38") (pinfunction "PE7_38") (pintype "passive"))
    )
    (net (code "112") (name "unconnected-(DD2B-PE8-Pad39)") (class "Default")
      (node (ref "DD2") (pin "39") (pinfunction "PE8_39") (pintype "passive"))
    )
    (net (code "113") (name "unconnected-(DD2B-PE9-Pad40)") (class "Default")
      (node (ref "DD2") (pin "40") (pinfunction "PE9_40") (pintype "passive"))
    )
    (net (code "114") (name "unconnected-(DD2B-PE10-Pad41)") (class "Default")
      (node (ref "DD2") (pin "41") (pinfunction "PE10_41") (pintype "passive"))
    )
    (net (code "115") (name "unconnected-(DD2B-PE11-Pad42)") (class "Default")
      (node (ref "DD2") (pin "42") (pinfunction "PE11_42") (pintype "passive"))
    )
    (net (code "116") (name "unconnected-(DD2B-PE12-Pad43)") (class "Default")
      (node (ref "DD2") (pin "43") (pinfunction "PE12_43") (pintype "passive"))
    )
    (net (code "117") (name "unconnected-(DD2B-PE13-Pad44)") (class "Default")
      (node (ref "DD2") (pin "44") (pinfunction "PE13_44") (pintype "passive"))
    )
    (net (code "118") (name "unconnected-(DD2B-PE14-Pad45)") (class "Default")
      (node (ref "DD2") (pin "45") (pinfunction "PE14_45") (pintype "passive"))
    )
    (net (code "119") (name "unconnected-(DD2B-PE15-Pad46)") (class "Default")
      (node (ref "DD2") (pin "46") (pinfunction "PE15_46") (pintype "passive"))
    )
    (net (code "120") (name "unconnected-(DD3-R2_IN-Pad8)") (class "Default")
      (node (ref "DD3") (pin "8") (pinfunction "R2_IN_8") (pintype "passive"))
    )
    (net (code "121") (name "unconnected-(DD3-R2_OUT-Pad9)") (class "Default")
      (node (ref "DD3") (pin "9") (pinfunction "R2_OUT_9") (pintype "passive"))
    )
    (net (code "122") (name "unconnected-(DD3-T2_IN-Pad10)") (class "Default")
      (node (ref "DD3") (pin "10") (pinfunction "T2_IN_10") (pintype "passive"))
    )
    (net (code "123") (name "unconnected-(DD3-T2_OUT-Pad7)") (class "Default")
      (node (ref "DD3") (pin "7") (pinfunction "T2_OUT_7") (pintype "passive"))
    )
    (net (code "124") (name "unconnected-(HG1-DB0-Pad7)") (class "Default")
      (node (ref "HG1") (pin "7") (pinfunction "DB0_7") (pintype "passive"))
    )
    (net (code "125") (name "unconnected-(HG1-DB1-Pad8)") (class "Default")
      (node (ref "HG1") (pin "8") (pinfunction "DB1_8") (pintype "passive"))
    )
    (net (code "126") (name "unconnected-(HG1-DB2-Pad9)") (class "Default")
      (node (ref "HG1") (pin "9") (pinfunction "DB2_9") (pintype "passive"))
    )
    (net (code "127") (name "unconnected-(HG1-DB3-Pad10)") (class "Default")
      (node (ref "HG1") (pin "10") (pinfunction "DB3_10") (pintype "passive"))
    )
    (net (code "128") (name "unconnected-(HG2-DB0-Pad7)") (class "Default")
      (node (ref "HG2") (pin "7") (pinfunction "DB0_7") (pintype "passive"))
    )
    (net (code "129") (name "unconnected-(HG2-DB1-Pad8)") (class "Default")
      (node (ref "HG2") (pin "8") (pinfunction "DB1_8") (pintype "passive"))
    )
    (net (code "130") (name "unconnected-(HG2-DB2-Pad9)") (class "Default")
      (node (ref "HG2") (pin "9") (pinfunction "DB2_9") (pintype "passive"))
    )
    (net (code "131") (name "unconnected-(HG2-DB3-Pad10)") (class "Default")
      (node (ref "HG2") (pin "10") (pinfunction "DB3_10") (pintype "passive"))
    )
  )
)
